# PMI_Split.net
KiCad netlist of a schematic drawn in Altium Designer
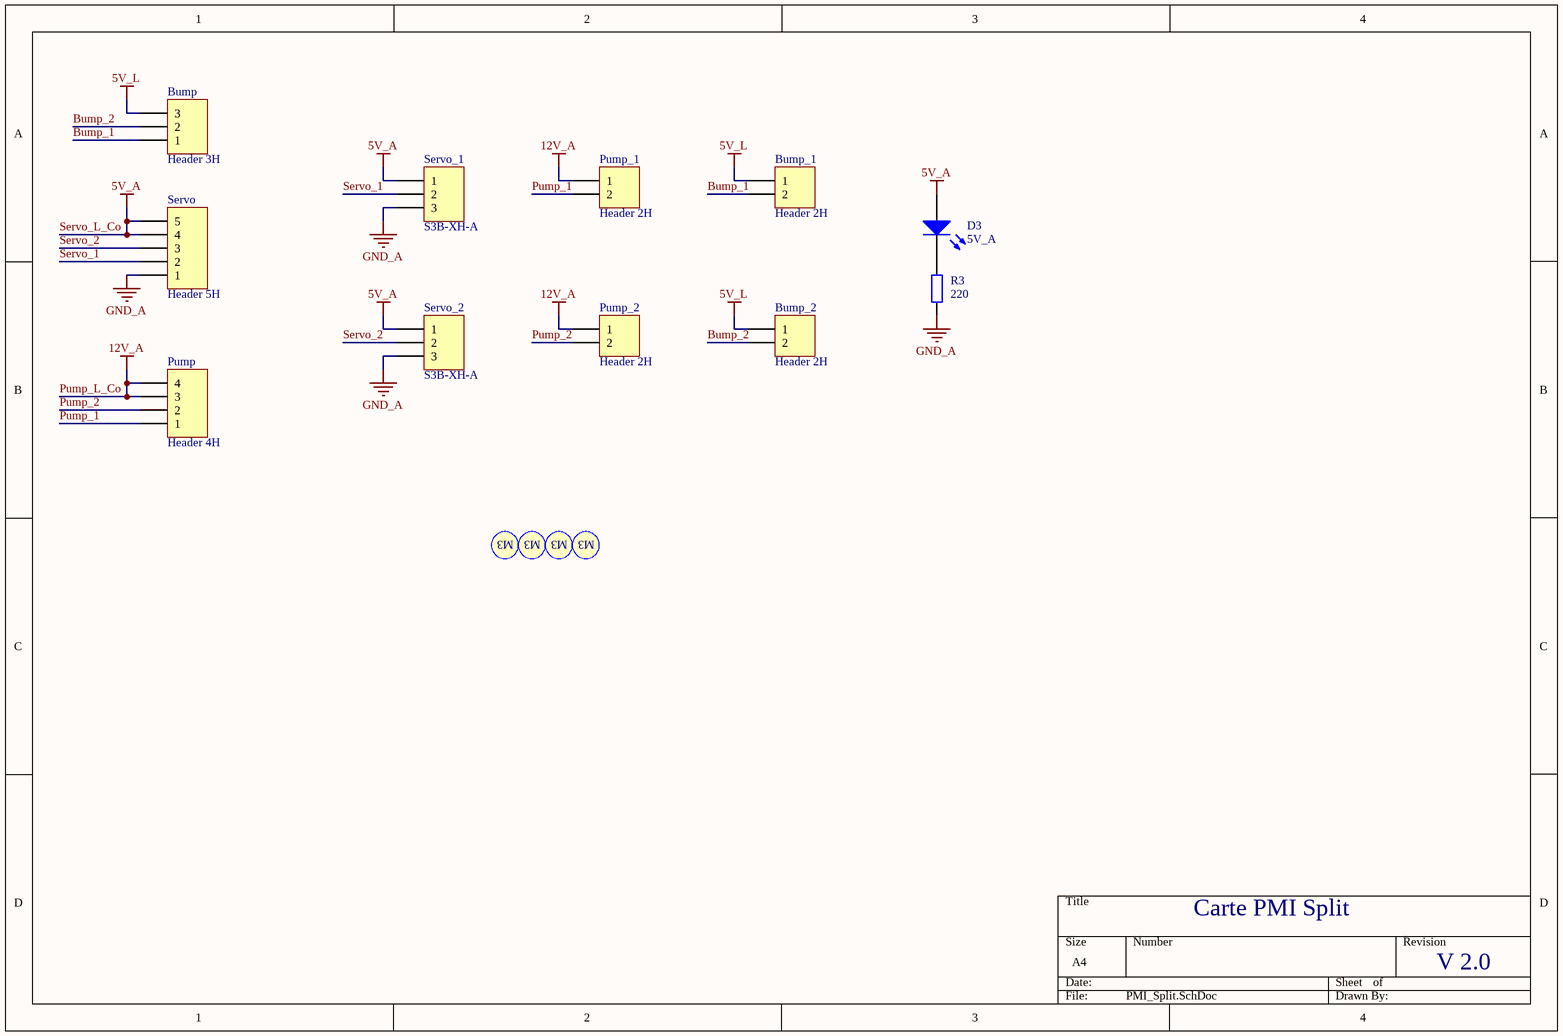
[diagram p0: PMI_Split.SchDoc]

(export (version "E")
  (design (tool "Eeschema 10.0.6"))
  (components
    (comp (ref "Bump")
      (value "Header 3H")
      (footprint "S3B-XH-A")
      (description "Header, 3-Pin, Right Angle")
      (fields (field (name "PUBLISHER") "Altium Limited"))
      (libsource (lib "") (part "Header 3H_1"))
    )
    (comp (ref "Bump_1")
      (value "Header 2H")
      (footprint "S2B-XH-A")
      (description "Header, 2-Pin, Right Angle")
      (fields (field (name "PUBLISHER") "Altium Limited"))
      (libsource (lib "Miscellaneous Connectors") (part "Header 2H"))
    )
    (comp (ref "Bump_2")
      (value "Header 2H")
      (footprint "S2B-XH-A")
      (description "Header, 2-Pin, Right Angle")
      (fields (field (name "PUBLISHER") "Altium Limited"))
      (libsource (lib "Miscellaneous Connectors") (part "Header 2H"))
    )
    (comp (ref "D3")
      (value "5V_A")
      (footprint "KP-3216SEC")
      (description "Typical RED, GREEN, YELLOW, AMBER GaAs LED")
      (fields (field (name "PUBLISHER") "Altium Limited"))
      (libsource (lib "Miscellaneous Devices") (part "LED2"))
    )
    (comp (ref "Pump")
      (value "Header 4H")
      (footprint "S4B-XH-A")
      (description "Header, 4-Pin, Right Angle")
      (fields (field (name "PUBLISHER") "Altium Limited"))
      (libsource (lib "Miscellaneous Connectors") (part "Header 4H"))
    )
    (comp (ref "Pump_1")
      (value "Header 2H")
      (footprint "S2B-XH-A")
      (description "Header, 2-Pin, Right Angle")
      (fields (field (name "PUBLISHER") "Altium Limited"))
      (libsource (lib "Miscellaneous Connectors") (part "Header 2H"))
    )
    (comp (ref "Pump_2")
      (value "Header 2H")
      (footprint "S2B-XH-A")
      (description "Header, 2-Pin, Right Angle")
      (fields (field (name "PUBLISHER") "Altium Limited"))
      (libsource (lib "Miscellaneous Connectors") (part "Header 2H"))
    )
    (comp (ref "R3")
      (value "220")
      (footprint "Resistor 1206")
      (description "Resistor")
      (fields (field (name "Comment") "Res2") (field (name "PUBLISHER") "Altium Limited"))
      (libsource (lib "Miscellaneous Devices") (part "Res2"))
    )
    (comp (ref "S1")
      (value "Screw M3")
      (footprint "Screw M3")
      (libsource (lib "Robot_2020") (part "Screw M3"))
    )
    (comp (ref "S2")
      (value "Screw M3")
      (footprint "Screw M3")
      (libsource (lib "Robot_2020") (part "Screw M3"))
    )
    (comp (ref "S3")
      (value "Screw M3")
      (footprint "Screw M3")
      (libsource (lib "Robot_2020") (part "Screw M3"))
    )
    (comp (ref "S4")
      (value "Screw M3")
      (footprint "Screw M3")
      (libsource (lib "Robot_2020") (part "Screw M3"))
    )
    (comp (ref "Servo")
      (value "Header 5H")
      (footprint "S5B-XH-A")
      (description "Header, 5-Pin, Right Angle")
      (fields (field (name "PUBLISHER") "Altium Limited"))
      (libsource (lib "Miscellaneous Connectors") (part "Header 5H"))
    )
    (comp (ref "Servo_1")
      (value "S3B-XH-A")
      (footprint "S3B-XH-A")
      (description "Header, 3-Pin, Right Angle")
      (fields (field (name "PUBLISHER") "Altium Limited"))
      (libsource (lib "Miscellaneous Connectors") (part "Header 3H"))
    )
    (comp (ref "Servo_2")
      (value "S3B-XH-A")
      (footprint "S3B-XH-A")
      (description "Header, 3-Pin, Right Angle")
      (fields (field (name "PUBLISHER") "Altium Limited"))
      (libsource (lib "Miscellaneous Connectors") (part "Header 3H"))
    )
  )
  (nets
    (net (code "1") (name "/Bump_1") (class "Default")
      (node (ref "Bump") (pin "1") (pinfunction "1_1") (pintype "passive"))
      (node (ref "Bump_1") (pin "2") (pinfunction "2_2") (pintype "passive"))
    )
    (net (code "2") (name "/Bump_2") (class "Default")
      (node (ref "Bump") (pin "2") (pinfunction "2_2") (pintype "passive"))
      (node (ref "Bump_2") (pin "2") (pinfunction "2_2") (pintype "passive"))
    )
    (net (code "3") (name "/Pump_1") (class "Default")
      (node (ref "Pump") (pin "1") (pinfunction "1_1") (pintype "passive"))
      (node (ref "Pump_1") (pin "2") (pinfunction "2_2") (pintype "passive"))
    )
    (net (code "4") (name "/Pump_2") (class "Default")
      (node (ref "Pump") (pin "2") (pinfunction "2_2") (pintype "passive"))
      (node (ref "Pump_2") (pin "2") (pinfunction "2_2") (pintype "passive"))
    )
    (net (code "5") (name "/Servo_1") (class "Default")
      (node (ref "Servo") (pin "2") (pinfunction "2_2") (pintype "passive"))
      (node (ref "Servo_1") (pin "2") (pinfunction "2_2") (pintype "passive"))
    )
    (net (code "6") (name "/Servo_2") (class "Default")
      (node (ref "Servo") (pin "3") (pinfunction "3_3") (pintype "passive"))
      (node (ref "Servo_2") (pin "2") (pinfunction "2_2") (pintype "passive"))
    )
    (net (code "7") (name "5V_A") (class "Default")
      (node (ref "D3") (pin "1") (pinfunction "A_1") (pintype "passive"))
      (node (ref "Servo") (pin "4") (pinfunction "4_4") (pintype "passive"))
      (node (ref "Servo") (pin "5") (pinfunction "5_5") (pintype "passive"))
      (node (ref "Servo_1") (pin "1") (pinfunction "1_1") (pintype "passive"))
      (node (ref "Servo_2") (pin "1") (pinfunction "1_1") (pintype "passive"))
    )
    (net (code "8") (name "5V_L") (class "Default")
      (node (ref "Bump") (pin "3") (pinfunction "3_3") (pintype "passive"))
      (node (ref "Bump_1") (pin "1") (pinfunction "1_1") (pintype "passive"))
      (node (ref "Bump_2") (pin "1") (pinfunction "1_1") (pintype "passive"))
    )
    (net (code "9") (name "12V_A") (class "Default")
      (node (ref "Pump") (pin "3") (pinfunction "3_3") (pintype "passive"))
      (node (ref "Pump") (pin "4") (pinfunction "4_4") (pintype "passive"))
      (node (ref "Pump_1") (pin "1") (pinfunction "1_1") (pintype "passive"))
      (node (ref "Pump_2") (pin "1") (pinfunction "1_1") (pintype "passive"))
    )
    (net (code "10") (name "GND_A") (class "Default")
      (node (ref "R3") (pin "2") (pinfunction "2_2") (pintype "passive"))
      (node (ref "Servo") (pin "1") (pinfunction "1_1") (pintype "passive"))
      (node (ref "Servo_1") (pin "3") (pinfunction "3_3") (pintype "passive"))
      (node (ref "Servo_2") (pin "3") (pinfunction "3_3") (pintype "passive"))
    )
    (net (code "11") (name "Net-(D3-K)") (class "Default")
      (node (ref "D3") (pin "2") (pinfunction "K_2") (pintype "passive"))
      (node (ref "R3") (pin "1") (pinfunction "1_1") (pintype "passive"))
    )
  )
)
